# 24V_Buck_3_3V.net
KiCad netlist of a schematic drawn in Altium Designer
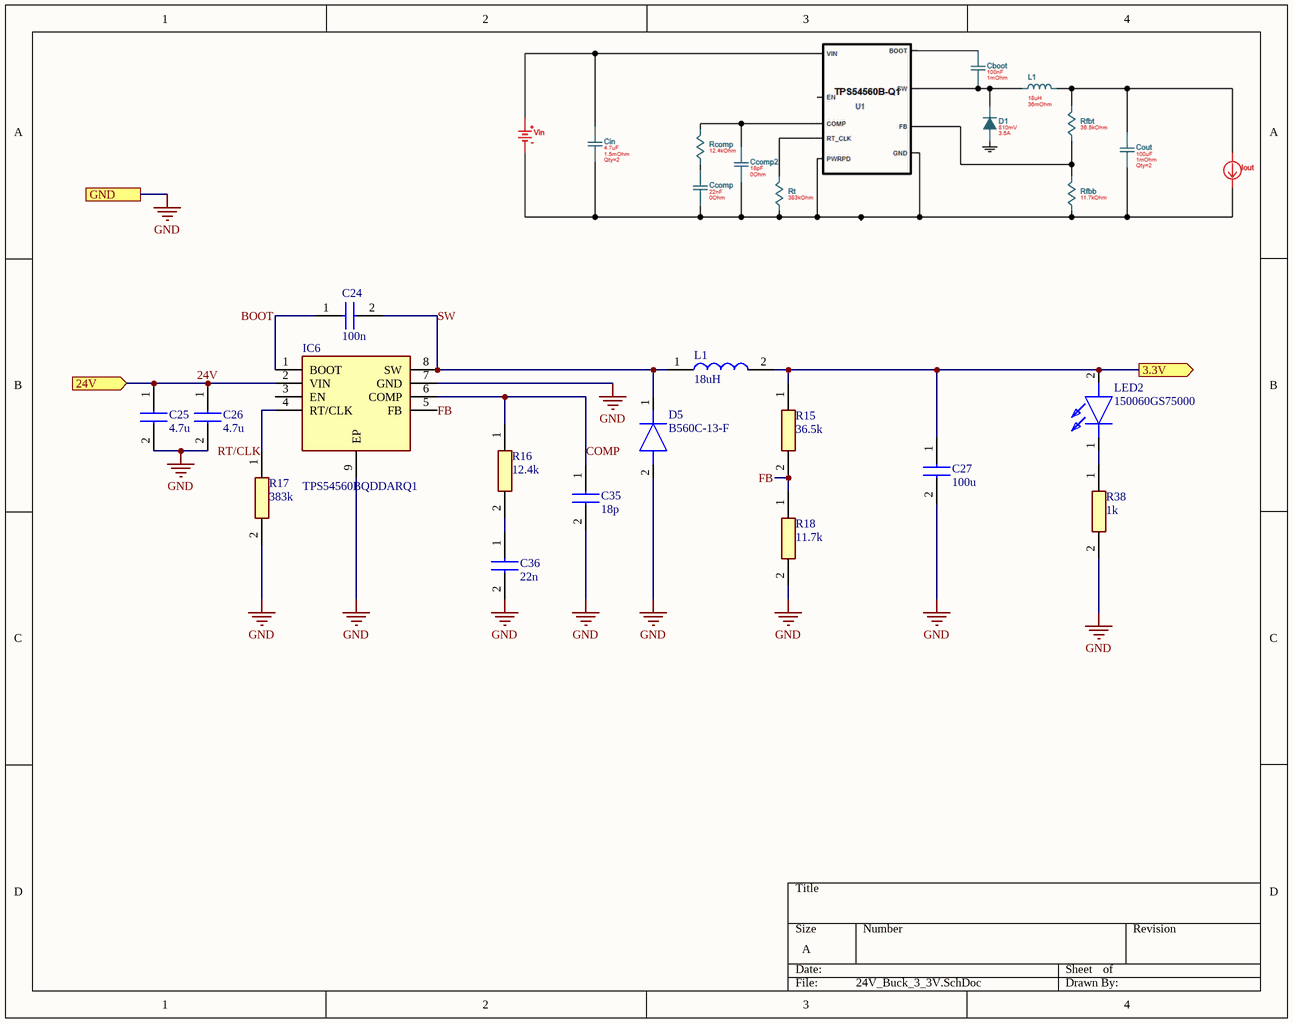
[diagram p0: 24V_Buck_3_3V.SchDoc]

(export (version "E")
  (design (tool "Eeschema 10.0.6"))
  (components
    (comp (ref "C24")
      (value "100n")
      (footprint "SamacSys:CAPC1608X90N")
      (description "Capacitor")
      (fields
        (field (name "MANUFACTURER_PART_NUMBER") "06035C104J4Z2A")
        (field (name "MOUSER PART NUMBER") "581-06035C104J4Z2A")
      )
      (libsource (lib "*") (part "06035C104J4Z2A"))
    )
    (comp (ref "C25")
      (value "4.7u")
      (footprint "SamacSys:CAPC2012X145N")
      (description "Capacitor")
      (fields
        (field (name "MANUFACTURER_PART_NUMBER") "GRM21BR61H475ME51L")
        (field (name "MOUSER PART NUMBER") "81-GRM21BR61H475M51L")
      )
      (libsource (lib "*") (part "GRM21BR61H475ME51L"))
    )
    (comp (ref "C26")
      (value "4.7u")
      (footprint "SamacSys:CAPC2012X145N")
      (description "Capacitor")
      (fields
        (field (name "MANUFACTURER_PART_NUMBER") "GRM21BR61H475ME51L")
        (field (name "MOUSER PART NUMBER") "81-GRM21BR61H475M51L")
      )
      (libsource (lib "*") (part "GRM21BR61H475ME51L"))
    )
    (comp (ref "C27")
      (value "100u")
      (footprint "SamacSys:CAPC3216X190N")
      (description "Capacitor")
      (fields
        (field (name "MANUFACTURER_PART_NUMBER") "CL31X107MQKNNWE")
        (field (name "MOUSER PART NUMBER") "187-CL31X107MQKNNWE")
      )
      (libsource (lib "*") (part "CL31X107MQKNNWE"))
    )
    (comp (ref "C35")
      (value "18p")
      (footprint "SamacSys:CAPC1608X90N")
      (description "Capacitor")
      (fields
        (field (name "MANUFACTURER_PART_NUMBER") "06035A180JAT4A")
        (field (name "MOUSER PART NUMBER") "581-06035A180JAT4A")
      )
      (libsource (lib "*") (part "06035A180JAT4A"))
    )
    (comp (ref "C36")
      (value "22n")
      (footprint "SamacSys:CAPC1608X87N")
      (description "Capacitor")
      (fields (field (name "MANUFACTURER_PART_NUMBER") "C0603C223K5RAC-TU"))
      (libsource (lib "*") (part "C0603C223K5RAC-TU"))
    )
    (comp (ref "D5")
      (value "B560C-13-F")
      (footprint "SamacSys:DIOM7959X250N")
      (description "Diode")
      (fields (field (name "MOUSER PART NUMBER") "621-B560C-F"))
      (libsource (lib "SamacSys") (part "B560C-13-F"))
    )
    (comp (ref "IC6")
      (value "TPS54560BQDDARQ1")
      (footprint "SamacSys:SOIC127P600X170-9N")
      (description "Integrated Circuit")
      (fields (field (name "MOUSER PART NUMBER") "595-TPS54560BQDDARQ1"))
      (libsource (lib "*") (part "TPS54560BQDDARQ1"))
    )
    (comp (ref "L1")
      (value "18uH")
      (footprint "SamacSys:INDPM125125X800N")
      (description "Inductor")
      (fields
        (field (name "MANUFACTURER_PART_NUMBER") "SRR1280-180M")
        (field (name "MOUSER PART NUMBER") "652-SRR1280-180M")
      )
      (libsource (lib "*") (part "SRR1280-180M"))
    )
    (comp (ref "LED2")
      (value "150060GS75000")
      (footprint "SamacSys:LEDC1608X70N")
      (description "LED")
      (fields (field (name "MOUSER PART NUMBER") "710-150060GS75000"))
      (libsource (lib "*") (part "150060GS75000"))
    )
    (comp (ref "R15")
      (value "36.5k")
      (footprint "SamacSys:RESC1608X55N")
      (description "Resistor")
      (fields
        (field (name "MANUFACTURER_PART_NUMBER") "ERJ-3EKF3652V")
        (field (name "MOUSER PART NUMBER") "667-ERJ-3EKF3652V")
      )
      (libsource (lib "*") (part "ERJ-3EKF3652V"))
    )
    (comp (ref "R16")
      (value "12.4k")
      (footprint "SamacSys:RESC1608X50N")
      (description "Resistor")
      (fields
        (field (name "MANUFACTURER_PART_NUMBER") "CRCW060312K4FKEA")
        (field (name "MOUSER PART NUMBER") "71-CRCW0603-12.4K-E3")
      )
      (libsource (lib "*") (part "CRCW060312K4FKEA"))
    )
    (comp (ref "R17")
      (value "383k")
      (footprint "SamacSys:RESC1608X55N")
      (description "Resistor")
      (fields
        (field (name "MANUFACTURER_PART_NUMBER") "ERJ-3EKF3833V")
        (field (name "MOUSER PART NUMBER") "667-ERJ-3EKF3833V")
      )
      (libsource (lib "*") (part "ERJ-3EKF3833V"))
    )
    (comp (ref "R18")
      (value "11.7k")
      (footprint "SamacSys:CAPC1608X55N")
      (description "Resistor")
      (fields
        (field (name "MANUFACTURER_PART_NUMBER") "TNPW060311K7BEEA")
        (field (name "MOUSER PART NUMBER") "71-TNPW060311K7BEEA")
      )
      (libsource (lib "*") (part "TNPW060311K7BEEA"))
    )
    (comp (ref "R38")
      (value "1k")
      (footprint "SamacSys:RESC1608X55N")
      (description "Resistor")
      (fields
        (field (name "MANUFACTURER_PART_NUMBER") "RMCF0603JT1K00")
        (field (name "MOUSER PART NUMBER") "708-RMCF0603JT1K00")
      )
      (libsource (lib "*") (part "RMCF0603JT1K00"))
    )
  )
  (nets
    (net (code "1") (name "/3.3V") (class "Default")
      (node (ref "C27") (pin "1") (pinfunction "1_1") (pintype "passive"))
      (node (ref "L1") (pin "2") (pinfunction "2_2") (pintype "passive"))
      (node (ref "LED2") (pin "2") (pinfunction "A_2") (pintype "passive"))
      (node (ref "R15") (pin "1") (pinfunction "1_1") (pintype "passive"))
    )
    (net (code "2") (name "/24V") (class "Default")
      (node (ref "C25") (pin "1") (pinfunction "1_1") (pintype "passive"))
      (node (ref "C26") (pin "1") (pinfunction "1_1") (pintype "passive"))
      (node (ref "IC6") (pin "2") (pinfunction "VIN_2") (pintype "passive"))
    )
    (net (code "3") (name "/BOOT") (class "Default")
      (node (ref "C24") (pin "1") (pinfunction "1_1") (pintype "passive"))
      (node (ref "IC6") (pin "1") (pinfunction "BOOT_1") (pintype "passive"))
    )
    (net (code "4") (name "/COMP") (class "Default")
      (node (ref "C35") (pin "1") (pinfunction "1_1") (pintype "passive"))
      (node (ref "IC6") (pin "6") (pinfunction "COMP_6") (pintype "passive"))
      (node (ref "R16") (pin "1") (pinfunction "1_1") (pintype "passive"))
    )
    (net (code "5") (name "/FB") (class "Default")
      (node (ref "IC6") (pin "5") (pinfunction "FB_5") (pintype "passive"))
      (node (ref "R15") (pin "2") (pinfunction "2_2") (pintype "passive"))
      (node (ref "R18") (pin "1") (pinfunction "1_1") (pintype "passive"))
    )
    (net (code "6") (name "/RT{slash}CLK") (class "Default")
      (node (ref "IC6") (pin "4") (pinfunction "RT/CLK_4") (pintype "passive"))
      (node (ref "R17") (pin "1") (pinfunction "1_1") (pintype "passive"))
    )
    (net (code "7") (name "/SW") (class "Default")
      (node (ref "C24") (pin "2") (pinfunction "2_2") (pintype "passive"))
      (node (ref "D5") (pin "1") (pinfunction "K_1") (pintype "passive"))
      (node (ref "IC6") (pin "8") (pinfunction "SW_8") (pintype "passive"))
      (node (ref "L1") (pin "1") (pinfunction "1_1") (pintype "passive"))
    )
    (net (code "8") (name "GND") (class "Default")
      (node (ref "C25") (pin "2") (pinfunction "2_2") (pintype "passive"))
      (node (ref "C26") (pin "2") (pinfunction "2_2") (pintype "passive"))
      (node (ref "C27") (pin "2") (pinfunction "2_2") (pintype "passive"))
      (node (ref "C35") (pin "2") (pinfunction "2_2") (pintype "passive"))
      (node (ref "C36") (pin "2") (pinfunction "2_2") (pintype "passive"))
      (node (ref "D5") (pin "2") (pinfunction "A_2") (pintype "passive"))
      (node (ref "IC6") (pin "7") (pinfunction "GND_7") (pintype "passive"))
      (node (ref "IC6") (pin "9") (pinfunction "EP_9") (pintype "passive"))
      (node (ref "R17") (pin "2") (pinfunction "2_2") (pintype "passive"))
      (node (ref "R18") (pin "2") (pinfunction "2_2") (pintype "passive"))
      (node (ref "R38") (pin "2") (pinfunction "2_2") (pintype "passive"))
    )
    (net (code "9") (name "Net-(C36-Pad1)") (class "Default")
      (node (ref "C36") (pin "1") (pinfunction "1_1") (pintype "passive"))
      (node (ref "R16") (pin "2") (pinfunction "2_2") (pintype "passive"))
    )
    (net (code "10") (name "Net-(LED2-K)") (class "Default")
      (node (ref "LED2") (pin "1") (pinfunction "K_1") (pintype "passive"))
      (node (ref "R38") (pin "1") (pinfunction "1_1") (pintype "passive"))
    )
    (net (code "11") (name "unconnected-(IC6-EN-Pad3)") (class "Default")
      (node (ref "IC6") (pin "3") (pinfunction "EN_3") (pintype "passive"))
    )
  )
)
